# rs485.net
KiCad netlist of a schematic drawn in Altium Designer
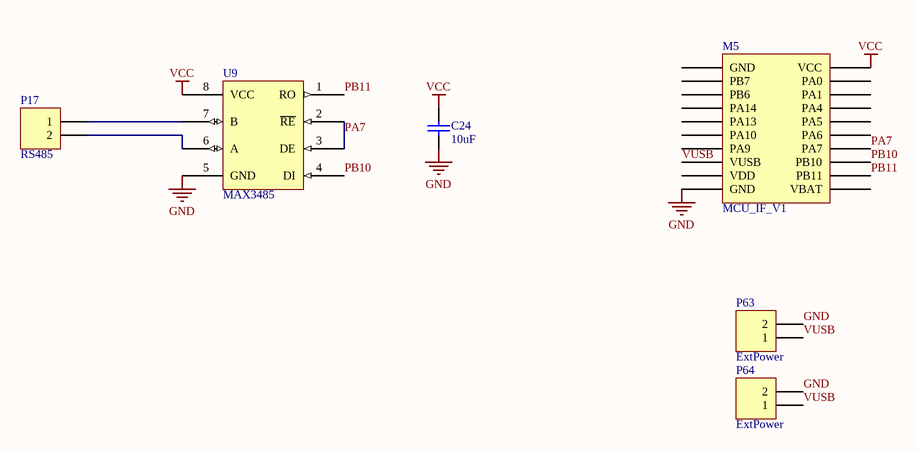
[diagram p0: rs485.SchDoc]

(export (version "E")
  (design (tool "Eeschema 10.0.6"))
  (components
    (comp (ref "C24")
      (value "10uF")
      (footprint "C-2012[0805]")
      (description "Capacitor (Semiconductor SIM Model)")
      (fields (field (name "Comment") "Cap Semi") (field (name "PUBLISHER") "Altium Limited"))
      (libsource (lib "Miscellaneous Devices") (part "Cap Semi"))
    )
    (comp (ref "M5")
      (value "MCU_IF_V1")
      (footprint "MCU_IF_V2")
      (libsource (lib "MCU_IF") (part "MCU_IF_V1"))
    )
    (comp (ref "P17")
      (value "RS485")
      (footprint "Edge5.08mm2P")
      (description "Header, 2-Pin")
      (fields (field (name "PUBLISHER") "Altium Limited"))
      (libsource (lib "Miscellaneous Connectors") (part "Header 2"))
    )
    (comp (ref "P63")
      (value "ExtPower")
      (footprint "HDR1X2H")
      (description "Header, 2-Pin, Right Angle")
      (fields (field (name "PUBLISHER") "Altium Limited"))
      (libsource (lib "Miscellaneous Connectors") (part "Header 2H"))
    )
    (comp (ref "P64")
      (value "ExtPower")
      (footprint "HDR1X2H")
      (description "Header, 2-Pin, Right Angle")
      (fields (field (name "PUBLISHER") "Altium Limited"))
      (libsource (lib "Miscellaneous Connectors") (part "Header 2H"))
    )
    (comp (ref "U9") (value "MAX3485") (footprint "SOP8") (libsource (lib "Schlib1") (part "MAX3485")))
  )
  (nets
    (net (code "1") (name "/PA7") (class "Default")
      (node (ref "M5") (pin "14") (pinfunction "PA7_14") (pintype "passive"))
      (node (ref "U9") (pin "2") (pinfunction "~{RE}_2") (pintype "input"))
      (node (ref "U9") (pin "3") (pinfunction "DE_3") (pintype "input"))
    )
    (net (code "2") (name "/PB10") (class "Default")
      (node (ref "M5") (pin "13") (pinfunction "PB10_13") (pintype "passive"))
      (node (ref "U9") (pin "4") (pinfunction "DI_4") (pintype "input"))
    )
    (net (code "3") (name "/PB11") (class "Default")
      (node (ref "M5") (pin "12") (pinfunction "PB11_12") (pintype "passive"))
      (node (ref "U9") (pin "1") (pinfunction "RO_1") (pintype "output"))
    )
    (net (code "4") (name "/VUSB") (class "Default")
      (node (ref "M5") (pin "8") (pinfunction "VUSB_8") (pintype "passive"))
      (node (ref "P63") (pin "1") (pinfunction "1_1") (pintype "passive"))
      (node (ref "P64") (pin "1") (pinfunction "1_1") (pintype "passive"))
    )
    (net (code "5") (name "GND") (class "Default")
      (node (ref "C24") (pin "2") (pinfunction "2_2") (pintype "passive"))
      (node (ref "M5") (pin "10") (pinfunction "GND_10") (pintype "passive"))
      (node (ref "P63") (pin "2") (pinfunction "2_2") (pintype "passive"))
      (node (ref "P64") (pin "2") (pinfunction "2_2") (pintype "passive"))
      (node (ref "U9") (pin "5") (pinfunction "GND_5") (pintype "power_in"))
    )
    (net (code "6") (name "Net-(U9-A)") (class "Default")
      (node (ref "P17") (pin "2") (pinfunction "2_2") (pintype "passive"))
      (node (ref "U9") (pin "6") (pinfunction "A_6") (pintype "bidirectional"))
    )
    (net (code "7") (name "Net-(U9-B)") (class "Default")
      (node (ref "P17") (pin "1") (pinfunction "1_1") (pintype "passive"))
      (node (ref "U9") (pin "7") (pinfunction "B_7") (pintype "bidirectional"))
    )
    (net (code "8") (name "VCC") (class "Default")
      (node (ref "C24") (pin "1") (pinfunction "1_1") (pintype "passive"))
      (node (ref "M5") (pin "20") (pinfunction "VCC_20") (pintype "passive"))
      (node (ref "U9") (pin "8") (pinfunction "VCC_8") (pintype "power_in"))
    )
    (net (code "9") (name "unconnected-(M5-GND-Pad1)") (class "Default")
      (node (ref "M5") (pin "1") (pinfunction "GND_1") (pintype "passive"))
    )
    (net (code "10") (name "unconnected-(M5-PA0-Pad19)") (class "Default")
      (node (ref "M5") (pin "19") (pinfunction "PA0_19") (pintype "passive"))
    )
    (net (code "11") (name "unconnected-(M5-PA1-Pad18)") (class "Default")
      (node (ref "M5") (pin "18") (pinfunction "PA1_18") (pintype "passive"))
    )
    (net (code "12") (name "unconnected-(M5-PA4-Pad17)") (class "Default")
      (node (ref "M5") (pin "17") (pinfunction "PA4_17") (pintype "passive"))
    )
    (net (code "13") (name "unconnected-(M5-PA5-Pad16)") (class "Default")
      (node (ref "M5") (pin "16") (pinfunction "PA5_16") (pintype "passive"))
    )
    (net (code "14") (name "unconnected-(M5-PA6-Pad15)") (class "Default")
      (node (ref "M5") (pin "15") (pinfunction "PA6_15") (pintype "passive"))
    )
    (net (code "15") (name "unconnected-(M5-PA9-Pad7)") (class "Default")
      (node (ref "M5") (pin "7") (pinfunction "PA9_7") (pintype "passive"))
    )
    (net (code "16") (name "unconnected-(M5-PA10-Pad6)") (class "Default")
      (node (ref "M5") (pin "6") (pinfunction "PA10_6") (pintype "passive"))
    )
    (net (code "17") (name "unconnected-(M5-PA13-Pad5)") (class "Default")
      (node (ref "M5") (pin "5") (pinfunction "PA13_5") (pintype "passive"))
    )
    (net (code "18") (name "unconnected-(M5-PA14-Pad4)") (class "Default")
      (node (ref "M5") (pin "4") (pinfunction "PA14_4") (pintype "passive"))
    )
    (net (code "19") (name "unconnected-(M5-PB6-Pad3)") (class "Default")
      (node (ref "M5") (pin "3") (pinfunction "PB6_3") (pintype "passive"))
    )
    (net (code "20") (name "unconnected-(M5-PB7-Pad2)") (class "Default")
      (node (ref "M5") (pin "2") (pinfunction "PB7_2") (pintype "passive"))
    )
    (net (code "21") (name "unconnected-(M5-VBAT-Pad11)") (class "Default")
      (node (ref "M5") (pin "11") (pinfunction "VBAT_11") (pintype "passive"))
    )
    (net (code "22") (name "unconnected-(M5-VDD-Pad9)") (class "Default")
      (node (ref "M5") (pin "9") (pinfunction "VDD_9") (pintype "passive"))
    )
  )
)
